# 1-Schematic_Trial_Project.net
KiCad netlist of a schematic drawn in EasyEDA
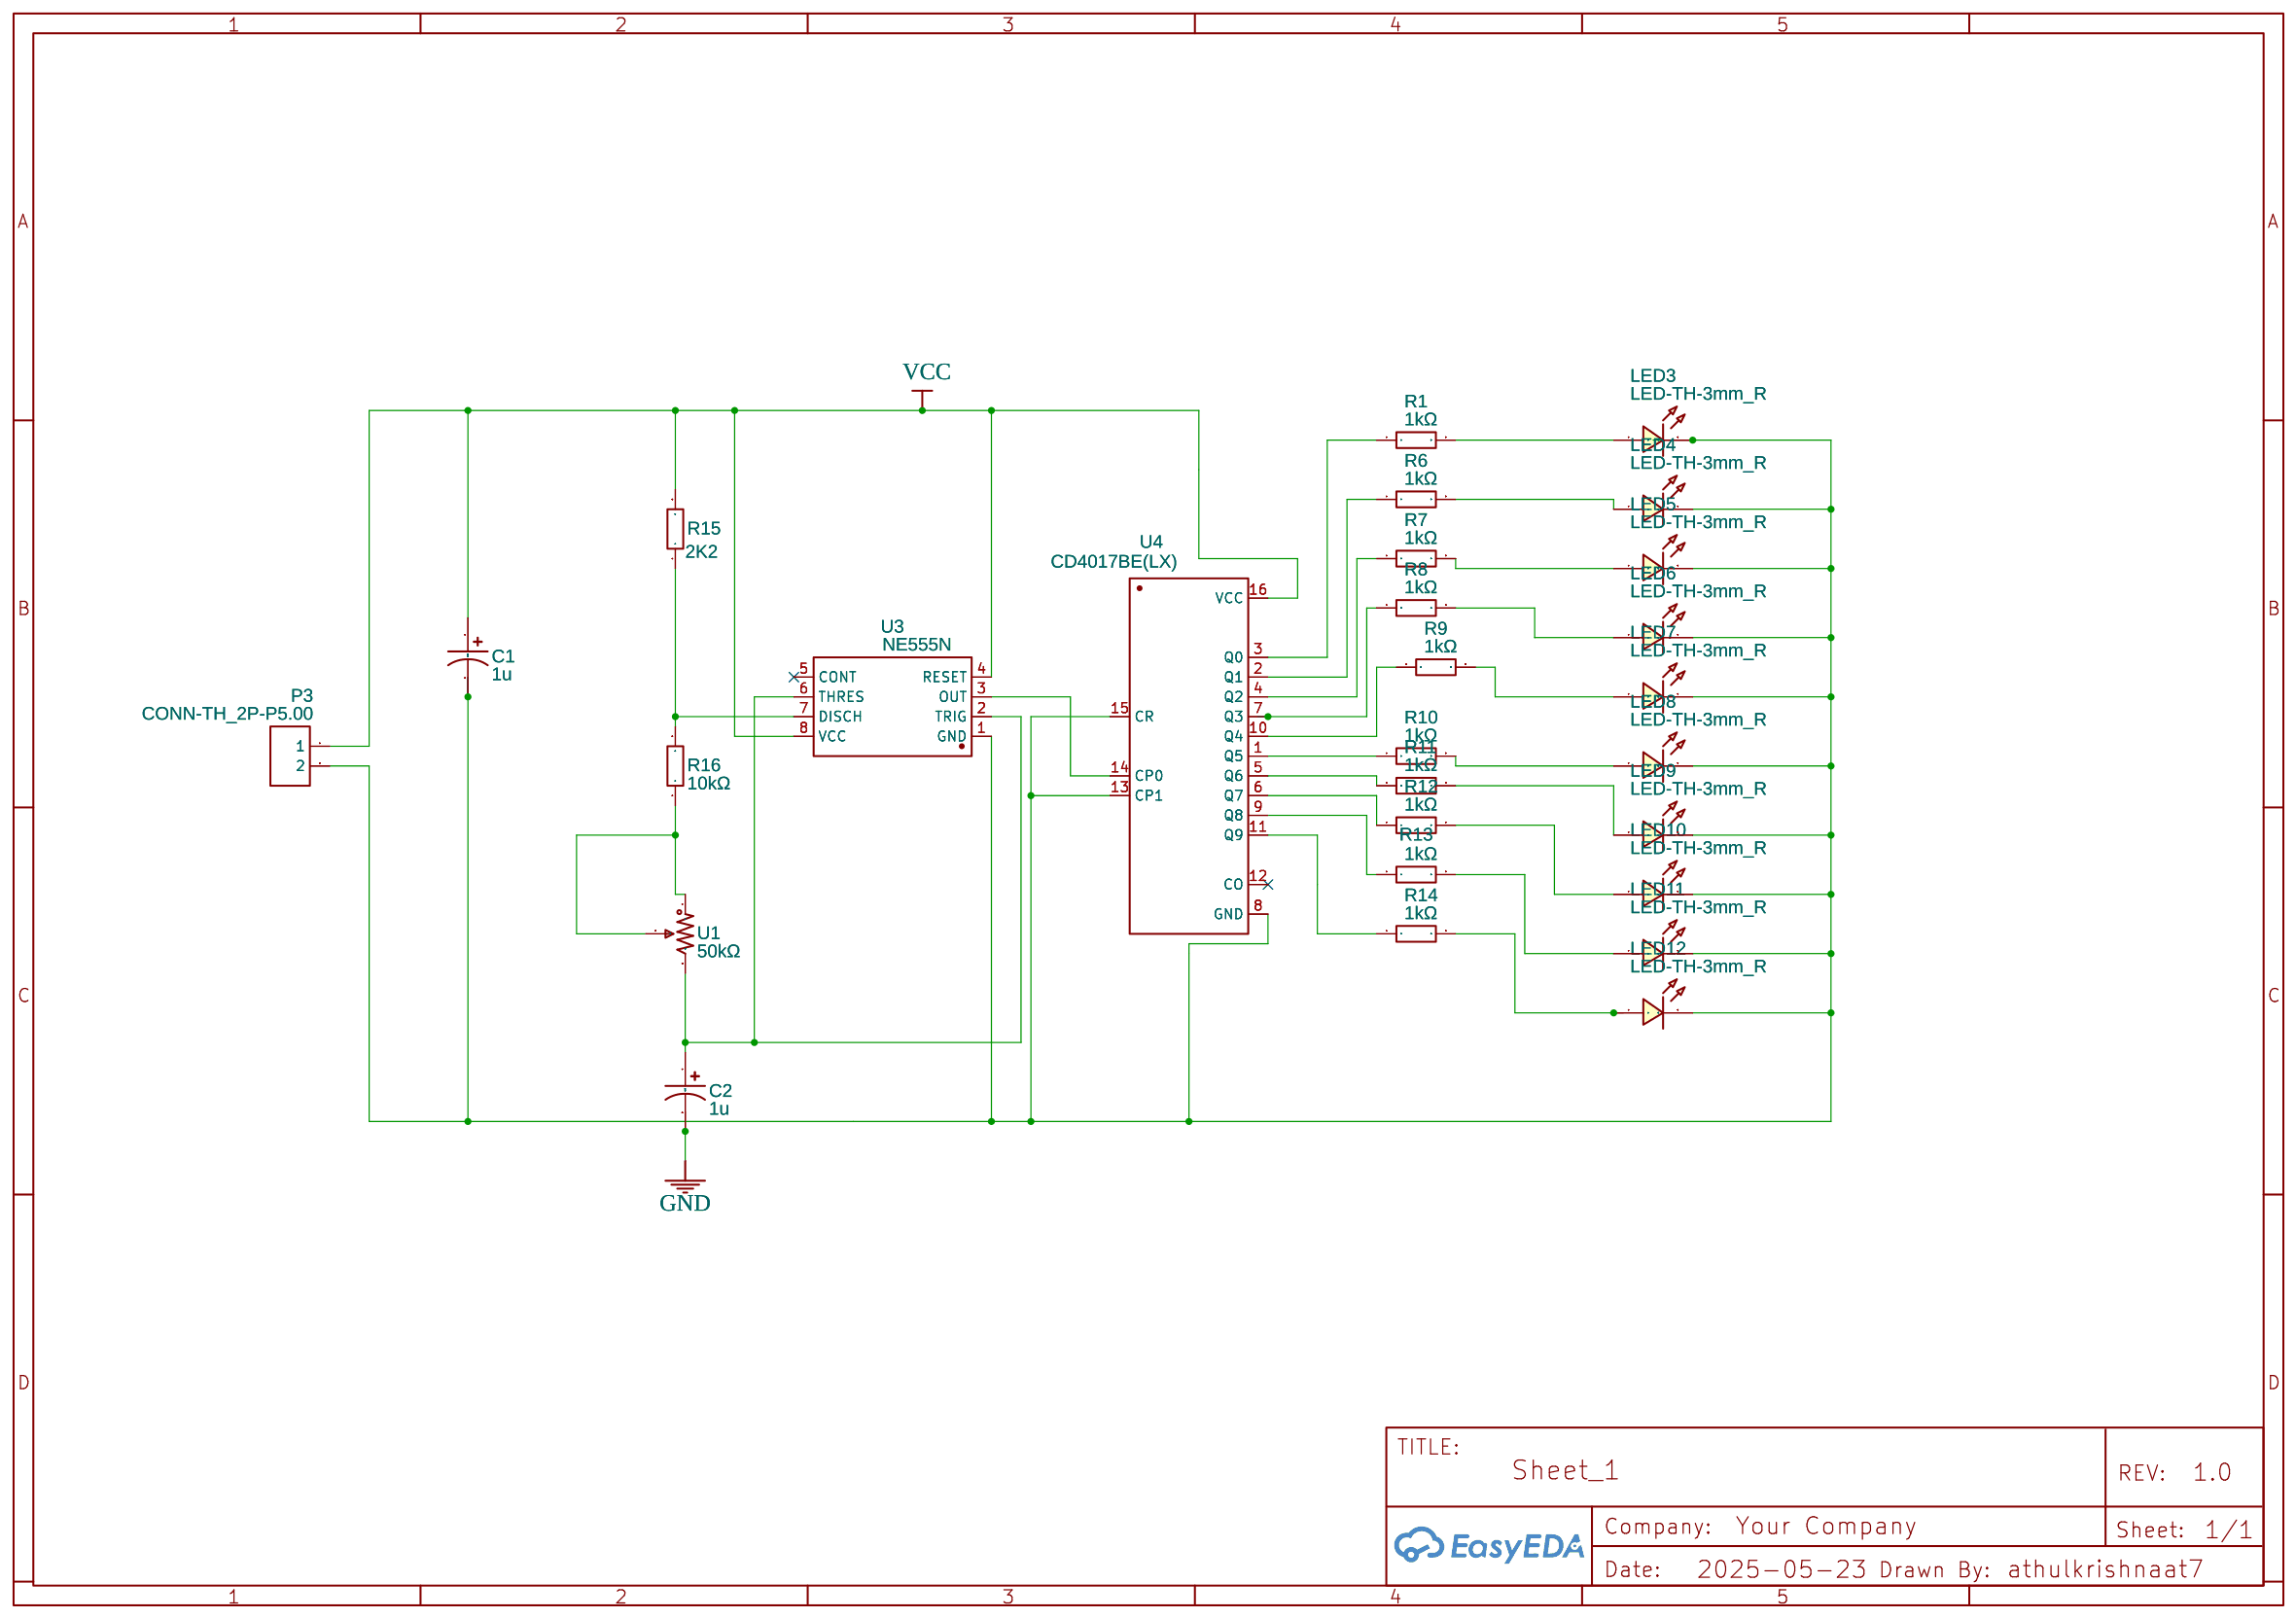
[diagram p0: schematic sheet]

(export (version "E")
  (design (tool "Eeschema 10.0.6"))
  (components
    (comp (ref "C1") (value "1u") (libsource (lib "") (part "C_Tan_SMD_A_US")))
    (comp (ref "C2") (value "1u") (libsource (lib "") (part "C_Tan_SMD_A_US_1")))
    (comp (ref "LED3")
      (value "LED-TH-3mm_R")
      (fields
        (field (name "Manufacturer Part") "204-10SDRD/S530-A3-L")
        (field (name "Manufacturer") "EVERLIGHT(台湾亿光)")
      )
      (libsource (lib "") (part "LED-TH-3mm_R"))
    )
    (comp (ref "LED4")
      (value "LED-TH-3mm_R")
      (fields
        (field (name "Manufacturer Part") "204-10SDRD/S530-A3-L")
        (field (name "Manufacturer") "EVERLIGHT(台湾亿光)")
      )
      (libsource (lib "") (part "LED-TH-3mm_R"))
    )
    (comp (ref "LED5")
      (value "LED-TH-3mm_R")
      (fields
        (field (name "Manufacturer Part") "204-10SDRD/S530-A3-L")
        (field (name "Manufacturer") "EVERLIGHT(台湾亿光)")
      )
      (libsource (lib "") (part "LED-TH-3mm_R"))
    )
    (comp (ref "LED6")
      (value "LED-TH-3mm_R")
      (fields
        (field (name "Manufacturer Part") "204-10SDRD/S530-A3-L")
        (field (name "Manufacturer") "EVERLIGHT(台湾亿光)")
      )
      (libsource (lib "") (part "LED-TH-3mm_R"))
    )
    (comp (ref "LED7")
      (value "LED-TH-3mm_R")
      (fields
        (field (name "Manufacturer Part") "204-10SDRD/S530-A3-L")
        (field (name "Manufacturer") "EVERLIGHT(台湾亿光)")
      )
      (libsource (lib "") (part "LED-TH-3mm_R"))
    )
    (comp (ref "LED8")
      (value "LED-TH-3mm_R")
      (fields
        (field (name "Manufacturer Part") "204-10SDRD/S530-A3-L")
        (field (name "Manufacturer") "EVERLIGHT(台湾亿光)")
      )
      (libsource (lib "") (part "LED-TH-3mm_R"))
    )
    (comp (ref "LED9")
      (value "LED-TH-3mm_R")
      (fields
        (field (name "Manufacturer Part") "204-10SDRD/S530-A3-L")
        (field (name "Manufacturer") "EVERLIGHT(台湾亿光)")
      )
      (libsource (lib "") (part "LED-TH-3mm_R"))
    )
    (comp (ref "LED10")
      (value "LED-TH-3mm_R")
      (fields
        (field (name "Manufacturer Part") "204-10SDRD/S530-A3-L")
        (field (name "Manufacturer") "EVERLIGHT(台湾亿光)")
      )
      (libsource (lib "") (part "LED-TH-3mm_R"))
    )
    (comp (ref "LED11")
      (value "LED-TH-3mm_R")
      (fields
        (field (name "Manufacturer Part") "204-10SDRD/S530-A3-L")
        (field (name "Manufacturer") "EVERLIGHT(台湾亿光)")
      )
      (libsource (lib "") (part "LED-TH-3mm_R"))
    )
    (comp (ref "LED12")
      (value "LED-TH-3mm_R")
      (fields
        (field (name "Manufacturer Part") "204-10SDRD/S530-A3-L")
        (field (name "Manufacturer") "EVERLIGHT(台湾亿光)")
      )
      (libsource (lib "") (part "LED-TH-3mm_R"))
    )
    (comp (ref "P3") (value "CONN-TH_2P-P5.00") (libsource (lib "") (part "CONN-TH_2P-P5.00")))
    (comp (ref "R1")
      (value "1kΩ")
      (fields (field (name "Manufacturer Part") "CR1210J30102G") (field (name "Manufacturer") "LIZ(丽智电子)"))
      (libsource (lib "") (part "CR1210J30102G_1"))
    )
    (comp (ref "R6")
      (value "1kΩ")
      (fields (field (name "Manufacturer Part") "CR1210J30102G") (field (name "Manufacturer") "LIZ(丽智电子)"))
      (libsource (lib "") (part "CR1210J30102G_1"))
    )
    (comp (ref "R7")
      (value "1kΩ")
      (fields (field (name "Manufacturer Part") "CR1210J30102G") (field (name "Manufacturer") "LIZ(丽智电子)"))
      (libsource (lib "") (part "CR1210J30102G_1"))
    )
    (comp (ref "R8")
      (value "1kΩ")
      (fields (field (name "Manufacturer Part") "CR1210J30102G") (field (name "Manufacturer") "LIZ(丽智电子)"))
      (libsource (lib "") (part "CR1210J30102G_1"))
    )
    (comp (ref "R9")
      (value "1kΩ")
      (fields (field (name "Manufacturer Part") "CR1210J30102G") (field (name "Manufacturer") "LIZ(丽智电子)"))
      (libsource (lib "") (part "CR1210J30102G_1"))
    )
    (comp (ref "R10")
      (value "1kΩ")
      (fields (field (name "Manufacturer Part") "CR1210J30102G") (field (name "Manufacturer") "LIZ(丽智电子)"))
      (libsource (lib "") (part "CR1210J30102G_1"))
    )
    (comp (ref "R11")
      (value "1kΩ")
      (fields (field (name "Manufacturer Part") "CR1210J30102G") (field (name "Manufacturer") "LIZ(丽智电子)"))
      (libsource (lib "") (part "CR1210J30102G_1"))
    )
    (comp (ref "R12")
      (value "1kΩ")
      (fields (field (name "Manufacturer Part") "CR1210J30102G") (field (name "Manufacturer") "LIZ(丽智电子)"))
      (libsource (lib "") (part "CR1210J30102G_1"))
    )
    (comp (ref "R13")
      (value "1kΩ")
      (fields (field (name "Manufacturer Part") "CR1210J30102G") (field (name "Manufacturer") "LIZ(丽智电子)"))
      (libsource (lib "") (part "CR1210J30102G_1"))
    )
    (comp (ref "R14")
      (value "1kΩ")
      (fields (field (name "Manufacturer Part") "CR1210J30102G") (field (name "Manufacturer") "LIZ(丽智电子)"))
      (libsource (lib "") (part "CR1210J30102G_1"))
    )
    (comp (ref "R15")
      (value "2K2")
      (fields (field (name "Manufacturer Part") "CR1210J30102G") (field (name "Manufacturer") "LIZ(丽智电子)"))
      (libsource (lib "") (part "CR1210J30102G"))
    )
    (comp (ref "R16")
      (value "10kΩ")
      (fields (field (name "Manufacturer Part") "CR1210J30102G") (field (name "Manufacturer") "LIZ(丽智电子)"))
      (libsource (lib "") (part "CR1210J30102G"))
    )
    (comp (ref "U1")
      (value "50kΩ")
      (fields (field (name "Manufacturer Part") "67WR50KLF") (field (name "Manufacturer") "TT Electronics"))
      (libsource (lib "") (part "67WR50KLF"))
    )
    (comp (ref "U3")
      (value "NE555N")
      (fields (field (name "Manufacturer") "HGSEMI(华冠)"))
      (libsource (lib "") (part "NE555N"))
    )
    (comp (ref "U4")
      (value "CD4017BE(LX)")
      (fields (field (name "Manufacturer") "LX(灵星芯微)"))
      (libsource (lib "") (part "CD4017BE(LX)"))
    )
  )
  (nets
    (net (code "1") (name "GND") (class "Default")
      (node (ref "C1") (pin "2") (pinfunction "2_2") (pintype "unspecified"))
      (node (ref "C2") (pin "2") (pinfunction "2_2") (pintype "unspecified"))
      (node (ref "LED10") (pin "2") (pinfunction "2_2") (pintype "unspecified"))
      (node (ref "LED11") (pin "2") (pinfunction "2_2") (pintype "unspecified"))
      (node (ref "LED12") (pin "2") (pinfunction "2_2") (pintype "unspecified"))
      (node (ref "LED3") (pin "2") (pinfunction "2_2") (pintype "unspecified"))
      (node (ref "LED4") (pin "2") (pinfunction "2_2") (pintype "unspecified"))
      (node (ref "LED5") (pin "2") (pinfunction "2_2") (pintype "unspecified"))
      (node (ref "LED6") (pin "2") (pinfunction "2_2") (pintype "unspecified"))
      (node (ref "LED7") (pin "2") (pinfunction "2_2") (pintype "unspecified"))
      (node (ref "LED8") (pin "2") (pinfunction "2_2") (pintype "unspecified"))
      (node (ref "LED9") (pin "2") (pinfunction "2_2") (pintype "unspecified"))
      (node (ref "P3") (pin "2") (pinfunction "2_2") (pintype "unspecified"))
      (node (ref "U3") (pin "1") (pinfunction "GND_1") (pintype "unspecified"))
      (node (ref "U4") (pin "13") (pinfunction "CP1_13") (pintype "unspecified"))
      (node (ref "U4") (pin "15") (pinfunction "CR_15") (pintype "unspecified"))
      (node (ref "U4") (pin "8") (pinfunction "GND_8") (pintype "unspecified"))
    )
    (net (code "2") (name "Net-(LED3-Pad1)") (class "Default")
      (node (ref "LED3") (pin "1") (pinfunction "1_1") (pintype "unspecified"))
      (node (ref "R1") (pin "2") (pinfunction "2_2") (pintype "unspecified"))
    )
    (net (code "3") (name "Net-(LED4-Pad1)") (class "Default")
      (node (ref "LED4") (pin "1") (pinfunction "1_1") (pintype "unspecified"))
      (node (ref "R6") (pin "2") (pinfunction "2_2") (pintype "unspecified"))
    )
    (net (code "4") (name "Net-(LED5-Pad1)") (class "Default")
      (node (ref "LED5") (pin "1") (pinfunction "1_1") (pintype "unspecified"))
      (node (ref "R7") (pin "2") (pinfunction "2_2") (pintype "unspecified"))
    )
    (net (code "5") (name "Net-(LED6-Pad1)") (class "Default")
      (node (ref "LED6") (pin "1") (pinfunction "1_1") (pintype "unspecified"))
      (node (ref "R8") (pin "2") (pinfunction "2_2") (pintype "unspecified"))
    )
    (net (code "6") (name "Net-(LED7-Pad1)") (class "Default")
      (node (ref "LED7") (pin "1") (pinfunction "1_1") (pintype "unspecified"))
      (node (ref "R9") (pin "2") (pinfunction "2_2") (pintype "unspecified"))
    )
    (net (code "7") (name "Net-(LED8-Pad1)") (class "Default")
      (node (ref "LED8") (pin "1") (pinfunction "1_1") (pintype "unspecified"))
      (node (ref "R10") (pin "2") (pinfunction "2_2") (pintype "unspecified"))
    )
    (net (code "8") (name "Net-(LED9-Pad1)") (class "Default")
      (node (ref "LED9") (pin "1") (pinfunction "1_1") (pintype "unspecified"))
      (node (ref "R11") (pin "2") (pinfunction "2_2") (pintype "unspecified"))
    )
    (net (code "9") (name "Net-(LED10-Pad1)") (class "Default")
      (node (ref "LED10") (pin "1") (pinfunction "1_1") (pintype "unspecified"))
      (node (ref "R12") (pin "2") (pinfunction "2_2") (pintype "unspecified"))
    )
    (net (code "10") (name "Net-(LED11-Pad1)") (class "Default")
      (node (ref "LED11") (pin "1") (pinfunction "1_1") (pintype "unspecified"))
      (node (ref "R13") (pin "2") (pinfunction "2_2") (pintype "unspecified"))
    )
    (net (code "11") (name "Net-(LED12-Pad1)") (class "Default")
      (node (ref "LED12") (pin "1") (pinfunction "1_1") (pintype "unspecified"))
      (node (ref "R14") (pin "2") (pinfunction "2_2") (pintype "unspecified"))
    )
    (net (code "12") (name "Net-(R16-Pad1)") (class "Default")
      (node (ref "R16") (pin "1") (pinfunction "1_1") (pintype "unspecified"))
      (node (ref "U1") (pin "1") (pinfunction "1_1") (pintype "unspecified"))
      (node (ref "U1") (pin "2") (pinfunction "2_2") (pintype "unspecified"))
    )
    (net (code "13") (name "Net-(U3-DISCH)") (class "Default")
      (node (ref "R15") (pin "1") (pinfunction "1_1") (pintype "unspecified"))
      (node (ref "R16") (pin "2") (pinfunction "2_2") (pintype "unspecified"))
      (node (ref "U3") (pin "7") (pinfunction "DISCH_7") (pintype "unspecified"))
    )
    (net (code "14") (name "Net-(U3-OUT)") (class "Default")
      (node (ref "U3") (pin "3") (pinfunction "OUT_3") (pintype "unspecified"))
      (node (ref "U4") (pin "14") (pinfunction "CP0_14") (pintype "unspecified"))
    )
    (net (code "15") (name "Net-(U3-THRES)") (class "Default")
      (node (ref "C2") (pin "1") (pinfunction "1_1") (pintype "unspecified"))
      (node (ref "U1") (pin "3") (pinfunction "3_3") (pintype "unspecified"))
      (node (ref "U3") (pin "2") (pinfunction "TRIG_2") (pintype "unspecified"))
      (node (ref "U3") (pin "6") (pinfunction "THRES_6") (pintype "unspecified"))
    )
    (net (code "16") (name "Net-(U4-Q0)") (class "Default")
      (node (ref "R1") (pin "1") (pinfunction "1_1") (pintype "unspecified"))
      (node (ref "U4") (pin "3") (pinfunction "Q0_3") (pintype "unspecified"))
    )
    (net (code "17") (name "Net-(U4-Q1)") (class "Default")
      (node (ref "R6") (pin "1") (pinfunction "1_1") (pintype "unspecified"))
      (node (ref "U4") (pin "2") (pinfunction "Q1_2") (pintype "unspecified"))
    )
    (net (code "18") (name "Net-(U4-Q2)") (class "Default")
      (node (ref "R7") (pin "1") (pinfunction "1_1") (pintype "unspecified"))
      (node (ref "U4") (pin "4") (pinfunction "Q2_4") (pintype "unspecified"))
    )
    (net (code "19") (name "Net-(U4-Q3)") (class "Default")
      (node (ref "R8") (pin "1") (pinfunction "1_1") (pintype "unspecified"))
      (node (ref "U4") (pin "7") (pinfunction "Q3_7") (pintype "unspecified"))
    )
    (net (code "20") (name "Net-(U4-Q4)") (class "Default")
      (node (ref "R9") (pin "1") (pinfunction "1_1") (pintype "unspecified"))
      (node (ref "U4") (pin "10") (pinfunction "Q4_10") (pintype "unspecified"))
    )
    (net (code "21") (name "Net-(U4-Q5)") (class "Default")
      (node (ref "R10") (pin "1") (pinfunction "1_1") (pintype "unspecified"))
      (node (ref "U4") (pin "1") (pinfunction "Q5_1") (pintype "unspecified"))
    )
    (net (code "22") (name "Net-(U4-Q6)") (class "Default")
      (node (ref "R11") (pin "1") (pinfunction "1_1") (pintype "unspecified"))
      (node (ref "U4") (pin "5") (pinfunction "Q6_5") (pintype "unspecified"))
    )
    (net (code "23") (name "Net-(U4-Q7)") (class "Default")
      (node (ref "R12") (pin "1") (pinfunction "1_1") (pintype "unspecified"))
      (node (ref "U4") (pin "6") (pinfunction "Q7_6") (pintype "unspecified"))
    )
    (net (code "24") (name "Net-(U4-Q8)") (class "Default")
      (node (ref "R13") (pin "1") (pinfunction "1_1") (pintype "unspecified"))
      (node (ref "U4") (pin "9") (pinfunction "Q8_9") (pintype "unspecified"))
    )
    (net (code "25") (name "Net-(U4-Q9)") (class "Default")
      (node (ref "R14") (pin "1") (pinfunction "1_1") (pintype "unspecified"))
      (node (ref "U4") (pin "11") (pinfunction "Q9_11") (pintype "unspecified"))
    )
    (net (code "26") (name "VCC") (class "Default")
      (node (ref "C1") (pin "1") (pinfunction "1_1") (pintype "unspecified"))
      (node (ref "P3") (pin "1") (pinfunction "1_1") (pintype "unspecified"))
      (node (ref "R15") (pin "2") (pinfunction "2_2") (pintype "unspecified"))
      (node (ref "U3") (pin "4") (pinfunction "RESET_4") (pintype "unspecified"))
      (node (ref "U3") (pin "8") (pinfunction "VCC_8") (pintype "unspecified"))
      (node (ref "U4") (pin "16") (pinfunction "VCC_16") (pintype "unspecified"))
    )
    (net (code "27") (name "unconnected-(U3-CONT-Pad5)") (class "Default")
      (node (ref "U3") (pin "5") (pinfunction "CONT_5") (pintype "unspecified+no_connect"))
    )
    (net (code "28") (name "unconnected-(U4-CO-Pad12)") (class "Default")
      (node (ref "U4") (pin "12") (pinfunction "CO_12") (pintype "unspecified+no_connect"))
    )
  )
)
